# 1_P1_schdoc.net
KiCad netlist of a schematic drawn in Altium Designer
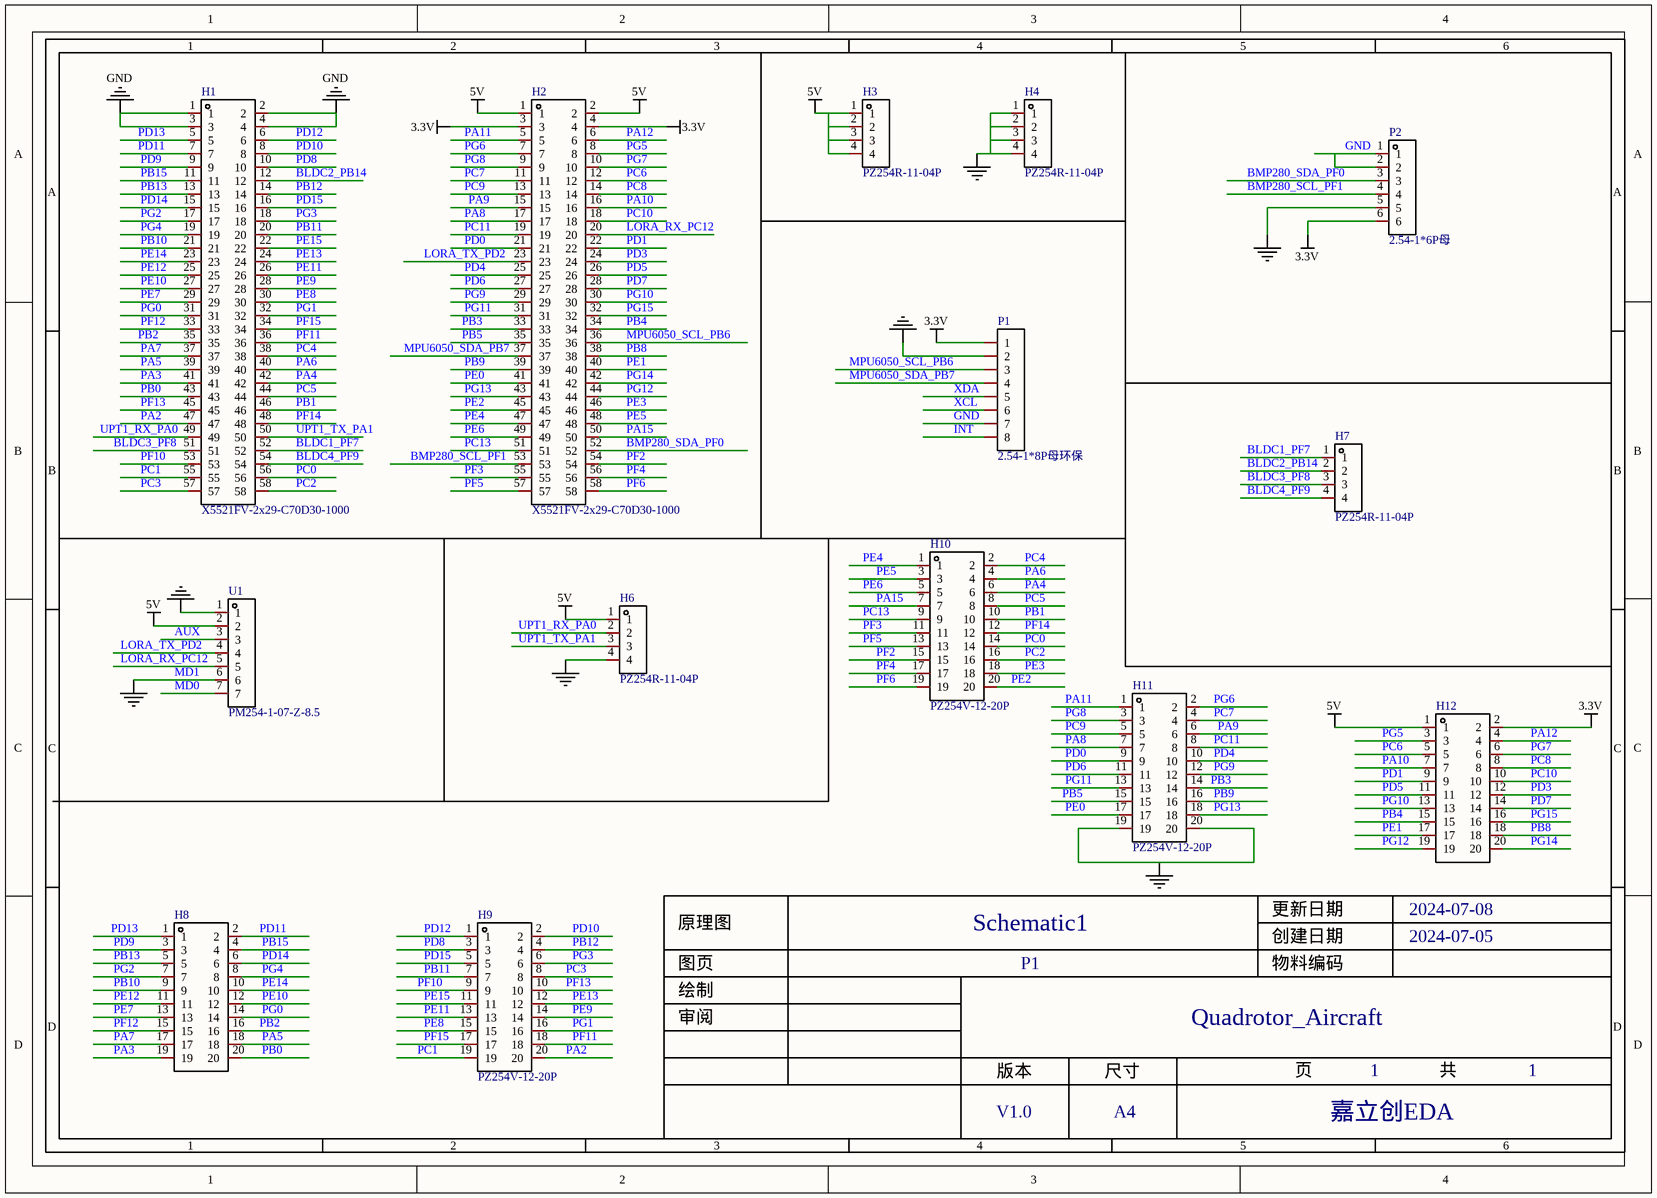
[diagram p0: 1_P1.schdoc.schdoc]

(export (version "E")
  (design (tool "Eeschema 10.0.6"))
  (components
    (comp (ref "H1")
      (value "X5521FV-2x29-C70D30-1000")
      (fields
        (field (name "NAME") "X5521FV-2x29-C70D30-1000")
        (field (name "MANUFACTURER") "XKB Connectivity(中国星坤)")
      )
      (libsource (lib "altium-import") (part "root_0_X5521FV-2x29-C70D30-1000_"))
    )
    (comp (ref "H2")
      (value "X5521FV-2x29-C70D30-1000")
      (fields
        (field (name "NAME") "X5521FV-2x29-C70D30-1000")
        (field (name "MANUFACTURER") "XKB Connectivity(中国星坤)")
      )
      (libsource (lib "altium-import") (part "root_0_X5521FV-2x29-C70D30-1000_"))
    )
    (comp (ref "H3")
      (value "PZ254R-11-04P")
      (fields (field (name "NAME") "PZ254R-11-04P") (field (name "MANUFACTURER") "XFCN(兴飞)"))
      (libsource (lib "altium-import") (part "root_0_PZ254R-11-04P_"))
    )
    (comp (ref "H4")
      (value "PZ254R-11-04P")
      (fields (field (name "NAME") "PZ254R-11-04P") (field (name "MANUFACTURER") "XFCN(兴飞)"))
      (libsource (lib "altium-import") (part "root_0_PZ254R-11-04P_"))
    )
    (comp (ref "H6")
      (value "PZ254R-11-04P")
      (fields (field (name "NAME") "PZ254R-11-04P") (field (name "MANUFACTURER") "XFCN(兴飞)"))
      (libsource (lib "altium-import") (part "root_0_PZ254R-11-04P_"))
    )
    (comp (ref "H7")
      (value "PZ254R-11-04P")
      (fields (field (name "NAME") "PZ254R-11-04P") (field (name "MANUFACTURER") "XFCN(兴飞)"))
      (libsource (lib "altium-import") (part "root_0_PZ254R-11-04P_"))
    )
    (comp (ref "H8")
      (value "PZ254V-12-20P")
      (fields (field (name "MANUFACTURER") "XFCN(兴飞)"))
      (libsource (lib "altium-import") (part "root_0_PZ254V-12-20P_"))
    )
    (comp (ref "H9")
      (value "PZ254V-12-20P")
      (fields (field (name "NAME") "PZ254V-12-20P") (field (name "MANUFACTURER") "XFCN(兴飞)"))
      (libsource (lib "altium-import") (part "root_0_PZ254V-12-20P_"))
    )
    (comp (ref "H10")
      (value "PZ254V-12-20P")
      (fields (field (name "NAME") "PZ254V-12-20P") (field (name "MANUFACTURER") "XFCN(兴飞)"))
      (libsource (lib "altium-import") (part "root_0_PZ254V-12-20P_"))
    )
    (comp (ref "H11")
      (value "PZ254V-12-20P")
      (fields (field (name "NAME") "PZ254V-12-20P") (field (name "MANUFACTURER") "XFCN(兴飞)"))
      (libsource (lib "altium-import") (part "root_0_PZ254V-12-20P_"))
    )
    (comp (ref "H12")
      (value "PZ254V-12-20P")
      (fields (field (name "MANUFACTURER") "XFCN(兴飞)"))
      (libsource (lib "") (part "root_0_PZ254V-12-20P__1"))
    )
    (comp (ref "P1")
      (value "2.54-1*8P母环保")
      (description "插孔结构:1x8P;间距:2.54mm;行距:-;安装类型:直插;排数:单排;总孔位数:8P;塑高:-;触头材质:-;触头镀层:-;")
      (fields (field (name "NAME") "2.54-1*8P母环保") (field (name "MANUFACTURER") "BOOMELE(博穆精密)"))
      (libsource (lib "altium-import") (part "root_0_2.54-1*8P母环保_"))
    )
    (comp (ref "P2")
      (value "2.54-1*6P母")
      (description "插孔结构:1x6P;间距:2.54mm;行距:-;安装类型:直插;排数:单排;总孔位数:6P;塑高:-;触头材质:-;触头镀层:-;")
      (fields (field (name "NAME") "2.54-1*6P母") (field (name "MANUFACTURER") "BOOMELE(博穆精密)"))
      (libsource (lib "altium-import") (part "root_0_2.54-1*6P母_"))
    )
    (comp (ref "U1")
      (value "PM254-1-07-Z-8.5")
      (fields (field (name "NAME") "PM254-1-07-Z-8.5") (field (name "MANUFACTURER") "HCTL(华灿天禄)"))
      (libsource (lib "altium-import") (part "root_0_PM254-1-07-Z-8.5_"))
    )
  )
  (nets
    (net (code "1") (name "/AUX") (class "Default")
      (node (ref "U1") (pin "3") (pinfunction "3_3") (pintype "passive"))
    )
    (net (code "2") (name "/BLDC1_PF7") (class "Default")
      (node (ref "H1") (pin "52") (pinfunction "52_52") (pintype "passive"))
      (node (ref "H7") (pin "1") (pinfunction "1_1") (pintype "passive"))
    )
    (net (code "3") (name "/BLDC2_PB14") (class "Default")
      (node (ref "H1") (pin "12") (pinfunction "12_12") (pintype "passive"))
      (node (ref "H7") (pin "2") (pinfunction "2_2") (pintype "passive"))
    )
    (net (code "4") (name "/BLDC3_PF8") (class "Default")
      (node (ref "H1") (pin "51") (pinfunction "51_51") (pintype "passive"))
      (node (ref "H7") (pin "3") (pinfunction "3_3") (pintype "passive"))
    )
    (net (code "5") (name "/BLDC4_PF9") (class "Default")
      (node (ref "H1") (pin "54") (pinfunction "54_54") (pintype "passive"))
      (node (ref "H7") (pin "4") (pinfunction "4_4") (pintype "passive"))
    )
    (net (code "6") (name "/BMP280_SCL_PF1") (class "Default")
      (node (ref "H2") (pin "53") (pinfunction "53_53") (pintype "passive"))
      (node (ref "P2") (pin "4") (pinfunction "4_4") (pintype "passive"))
    )
    (net (code "7") (name "/BMP280_SDA_PF0") (class "Default")
      (node (ref "H2") (pin "52") (pinfunction "52_52") (pintype "passive"))
      (node (ref "P2") (pin "3") (pinfunction "3_3") (pintype "passive"))
    )
    (net (code "8") (name "/INT") (class "Default")
      (node (ref "P1") (pin "8") (pinfunction "8_8") (pintype "passive"))
    )
    (net (code "9") (name "/LORA_RX_PC12") (class "Default")
      (node (ref "H2") (pin "20") (pinfunction "20_20") (pintype "passive"))
      (node (ref "U1") (pin "5") (pinfunction "5_5") (pintype "passive"))
    )
    (net (code "10") (name "/LORA_TX_PD2") (class "Default")
      (node (ref "H2") (pin "23") (pinfunction "23_23") (pintype "passive"))
      (node (ref "U1") (pin "4") (pinfunction "4_4") (pintype "passive"))
    )
    (net (code "11") (name "/MD0") (class "Default")
      (node (ref "U1") (pin "7") (pinfunction "7_7") (pintype "passive"))
    )
    (net (code "12") (name "/MPU6050_SCL_PB6") (class "Default")
      (node (ref "H2") (pin "36") (pinfunction "36_36") (pintype "passive"))
      (node (ref "P1") (pin "3") (pinfunction "3_3") (pintype "passive"))
    )
    (net (code "13") (name "/MPU6050_SDA_PB7") (class "Default")
      (node (ref "H2") (pin "37") (pinfunction "37_37") (pintype "passive"))
      (node (ref "P1") (pin "4") (pinfunction "4_4") (pintype "passive"))
    )
    (net (code "14") (name "/PA2") (class "Default")
      (node (ref "H1") (pin "47") (pinfunction "47_47") (pintype "passive"))
      (node (ref "H9") (pin "20") (pinfunction "20_20") (pintype "passive"))
    )
    (net (code "15") (name "/PA3") (class "Default")
      (node (ref "H1") (pin "41") (pinfunction "41_41") (pintype "passive"))
      (node (ref "H8") (pin "19") (pinfunction "19_19") (pintype "passive"))
    )
    (net (code "16") (name "/PA4") (class "Default")
      (node (ref "H1") (pin "42") (pinfunction "42_42") (pintype "passive"))
      (node (ref "H10") (pin "6") (pinfunction "6_6") (pintype "passive"))
    )
    (net (code "17") (name "/PA5") (class "Default")
      (node (ref "H1") (pin "39") (pinfunction "39_39") (pintype "passive"))
      (node (ref "H8") (pin "18") (pinfunction "18_18") (pintype "passive"))
    )
    (net (code "18") (name "/PA6") (class "Default")
      (node (ref "H1") (pin "40") (pinfunction "40_40") (pintype "passive"))
      (node (ref "H10") (pin "4") (pinfunction "4_4") (pintype "passive"))
    )
    (net (code "19") (name "/PA7") (class "Default")
      (node (ref "H1") (pin "37") (pinfunction "37_37") (pintype "passive"))
      (node (ref "H8") (pin "17") (pinfunction "17_17") (pintype "passive"))
    )
    (net (code "20") (name "/PA8") (class "Default")
      (node (ref "H11") (pin "7") (pinfunction "7_7") (pintype "passive"))
      (node (ref "H2") (pin "17") (pinfunction "17_17") (pintype "passive"))
    )
    (net (code "21") (name "/PA9") (class "Default")
      (node (ref "H11") (pin "6") (pinfunction "6_6") (pintype "passive"))
      (node (ref "H2") (pin "15") (pinfunction "15_15") (pintype "passive"))
    )
    (net (code "22") (name "/PA10") (class "Default")
      (node (ref "H12") (pin "7") (pinfunction "7_7") (pintype "passive"))
      (node (ref "H2") (pin "16") (pinfunction "16_16") (pintype "passive"))
    )
    (net (code "23") (name "/PA11") (class "Default")
      (node (ref "H11") (pin "1") (pinfunction "1_1") (pintype "passive"))
      (node (ref "H2") (pin "5") (pinfunction "5_5") (pintype "passive"))
    )
    (net (code "24") (name "/PA12") (class "Default")
      (node (ref "H12") (pin "4") (pinfunction "4_4") (pintype "passive"))
      (node (ref "H2") (pin "6") (pinfunction "6_6") (pintype "passive"))
    )
    (net (code "25") (name "/PA15") (class "Default")
      (node (ref "H10") (pin "7") (pinfunction "7_7") (pintype "passive"))
      (node (ref "H2") (pin "50") (pinfunction "50_50") (pintype "passive"))
    )
    (net (code "26") (name "/PB0") (class "Default")
      (node (ref "H1") (pin "43") (pinfunction "43_43") (pintype "passive"))
      (node (ref "H8") (pin "20") (pinfunction "20_20") (pintype "passive"))
    )
    (net (code "27") (name "/PB1") (class "Default")
      (node (ref "H1") (pin "46") (pinfunction "46_46") (pintype "passive"))
      (node (ref "H10") (pin "10") (pinfunction "10_10") (pintype "passive"))
    )
    (net (code "28") (name "/PB2") (class "Default")
      (node (ref "H1") (pin "35") (pinfunction "35_35") (pintype "passive"))
      (node (ref "H8") (pin "16") (pinfunction "16_16") (pintype "passive"))
    )
    (net (code "29") (name "/PB3") (class "Default")
      (node (ref "H11") (pin "14") (pinfunction "14_14") (pintype "passive"))
      (node (ref "H2") (pin "33") (pinfunction "33_33") (pintype "passive"))
    )
    (net (code "30") (name "/PB4") (class "Default")
      (node (ref "H12") (pin "15") (pinfunction "15_15") (pintype "passive"))
      (node (ref "H2") (pin "34") (pinfunction "34_34") (pintype "passive"))
    )
    (net (code "31") (name "/PB5") (class "Default")
      (node (ref "H11") (pin "15") (pinfunction "15_15") (pintype "passive"))
      (node (ref "H2") (pin "35") (pinfunction "35_35") (pintype "passive"))
    )
    (net (code "32") (name "/PB8") (class "Default")
      (node (ref "H12") (pin "18") (pinfunction "18_18") (pintype "passive"))
      (node (ref "H2") (pin "38") (pinfunction "38_38") (pintype "passive"))
    )
    (net (code "33") (name "/PB9") (class "Default")
      (node (ref "H11") (pin "16") (pinfunction "16_16") (pintype "passive"))
      (node (ref "H2") (pin "39") (pinfunction "39_39") (pintype "passive"))
    )
    (net (code "34") (name "/PB10") (class "Default")
      (node (ref "H1") (pin "21") (pinfunction "21_21") (pintype "passive"))
      (node (ref "H8") (pin "9") (pinfunction "9_9") (pintype "passive"))
    )
    (net (code "35") (name "/PB11") (class "Default")
      (node (ref "H1") (pin "20") (pinfunction "20_20") (pintype "passive"))
      (node (ref "H9") (pin "7") (pinfunction "7_7") (pintype "passive"))
    )
    (net (code "36") (name "/PB12") (class "Default")
      (node (ref "H1") (pin "14") (pinfunction "14_14") (pintype "passive"))
      (node (ref "H9") (pin "4") (pinfunction "4_4") (pintype "passive"))
    )
    (net (code "37") (name "/PB13") (class "Default")
      (node (ref "H1") (pin "13") (pinfunction "13_13") (pintype "passive"))
      (node (ref "H8") (pin "5") (pinfunction "5_5") (pintype "passive"))
    )
    (net (code "38") (name "/PB15") (class "Default")
      (node (ref "H1") (pin "11") (pinfunction "11_11") (pintype "passive"))
      (node (ref "H8") (pin "4") (pinfunction "4_4") (pintype "passive"))
    )
    (net (code "39") (name "/PC0") (class "Default")
      (node (ref "H1") (pin "56") (pinfunction "56_56") (pintype "passive"))
      (node (ref "H10") (pin "14") (pinfunction "14_14") (pintype "passive"))
    )
    (net (code "40") (name "/PC1") (class "Default")
      (node (ref "H1") (pin "55") (pinfunction "55_55") (pintype "passive"))
      (node (ref "H9") (pin "19") (pinfunction "19_19") (pintype "passive"))
    )
    (net (code "41") (name "/PC2") (class "Default")
      (node (ref "H1") (pin "58") (pinfunction "58_58") (pintype "passive"))
      (node (ref "H10") (pin "16") (pinfunction "16_16") (pintype "passive"))
    )
    (net (code "42") (name "/PC3") (class "Default")
      (node (ref "H1") (pin "57") (pinfunction "57_57") (pintype "passive"))
      (node (ref "H9") (pin "8") (pinfunction "8_8") (pintype "passive"))
    )
    (net (code "43") (name "/PC4") (class "Default")
      (node (ref "H1") (pin "38") (pinfunction "38_38") (pintype "passive"))
      (node (ref "H10") (pin "2") (pinfunction "2_2") (pintype "passive"))
    )
    (net (code "44") (name "/PC5") (class "Default")
      (node (ref "H1") (pin "44") (pinfunction "44_44") (pintype "passive"))
      (node (ref "H10") (pin "8") (pinfunction "8_8") (pintype "passive"))
    )
    (net (code "45") (name "/PC6") (class "Default")
      (node (ref "H12") (pin "5") (pinfunction "5_5") (pintype "passive"))
      (node (ref "H2") (pin "12") (pinfunction "12_12") (pintype "passive"))
    )
    (net (code "46") (name "/PC7") (class "Default")
      (node (ref "H11") (pin "4") (pinfunction "4_4") (pintype "passive"))
      (node (ref "H2") (pin "11") (pinfunction "11_11") (pintype "passive"))
    )
    (net (code "47") (name "/PC8") (class "Default")
      (node (ref "H12") (pin "8") (pinfunction "8_8") (pintype "passive"))
      (node (ref "H2") (pin "14") (pinfunction "14_14") (pintype "passive"))
    )
    (net (code "48") (name "/PC9") (class "Default")
      (node (ref "H11") (pin "5") (pinfunction "5_5") (pintype "passive"))
      (node (ref "H2") (pin "13") (pinfunction "13_13") (pintype "passive"))
    )
    (net (code "49") (name "/PC10") (class "Default")
      (node (ref "H12") (pin "10") (pinfunction "10_10") (pintype "passive"))
      (node (ref "H2") (pin "18") (pinfunction "18_18") (pintype "passive"))
    )
    (net (code "50") (name "/PC11") (class "Default")
      (node (ref "H11") (pin "8") (pinfunction "8_8") (pintype "passive"))
      (node (ref "H2") (pin "19") (pinfunction "19_19") (pintype "passive"))
    )
    (net (code "51") (name "/PC13") (class "Default")
      (node (ref "H10") (pin "9") (pinfunction "9_9") (pintype "passive"))
      (node (ref "H2") (pin "51") (pinfunction "51_51") (pintype "passive"))
    )
    (net (code "52") (name "/PD0") (class "Default")
      (node (ref "H11") (pin "9") (pinfunction "9_9") (pintype "passive"))
      (node (ref "H2") (pin "21") (pinfunction "21_21") (pintype "passive"))
    )
    (net (code "53") (name "/PD1") (class "Default")
      (node (ref "H12") (pin "9") (pinfunction "9_9") (pintype "passive"))
      (node (ref "H2") (pin "22") (pinfunction "22_22") (pintype "passive"))
    )
    (net (code "54") (name "/PD3") (class "Default")
      (node (ref "H12") (pin "12") (pinfunction "12_12") (pintype "passive"))
      (node (ref "H2") (pin "24") (pinfunction "24_24") (pintype "passive"))
    )
    (net (code "55") (name "/PD4") (class "Default")
      (node (ref "H11") (pin "10") (pinfunction "10_10") (pintype "passive"))
      (node (ref "H2") (pin "25") (pinfunction "25_25") (pintype "passive"))
    )
    (net (code "56") (name "/PD5") (class "Default")
      (node (ref "H12") (pin "11") (pinfunction "11_11") (pintype "passive"))
      (node (ref "H2") (pin "26") (pinfunction "26_26") (pintype "passive"))
    )
    (net (code "57") (name "/PD6") (class "Default")
      (node (ref "H11") (pin "11") (pinfunction "11_11") (pintype "passive"))
      (node (ref "H2") (pin "27") (pinfunction "27_27") (pintype "passive"))
    )
    (net (code "58") (name "/PD7") (class "Default")
      (node (ref "H12") (pin "14") (pinfunction "14_14") (pintype "passive"))
      (node (ref "H2") (pin "28") (pinfunction "28_28") (pintype "passive"))
    )
    (net (code "59") (name "/PD8") (class "Default")
      (node (ref "H1") (pin "10") (pinfunction "10_10") (pintype "passive"))
      (node (ref "H9") (pin "3") (pinfunction "3_3") (pintype "passive"))
    )
    (net (code "60") (name "/PD9") (class "Default")
      (node (ref "H1") (pin "9") (pinfunction "9_9") (pintype "passive"))
      (node (ref "H8") (pin "3") (pinfunction "3_3") (pintype "passive"))
    )
    (net (code "61") (name "/PD10") (class "Default")
      (node (ref "H1") (pin "8") (pinfunction "8_8") (pintype "passive"))
      (node (ref "H9") (pin "2") (pinfunction "2_2") (pintype "passive"))
    )
    (net (code "62") (name "/PD11") (class "Default")
      (node (ref "H1") (pin "7") (pinfunction "7_7") (pintype "passive"))
      (node (ref "H8") (pin "2") (pinfunction "2_2") (pintype "passive"))
    )
    (net (code "63") (name "/PD12") (class "Default")
      (node (ref "H1") (pin "6") (pinfunction "6_6") (pintype "passive"))
      (node (ref "H9") (pin "1") (pinfunction "1_1") (pintype "passive"))
    )
    (net (code "64") (name "/PD13") (class "Default")
      (node (ref "H1") (pin "5") (pinfunction "5_5") (pintype "passive"))
      (node (ref "H8") (pin "1") (pinfunction "1_1") (pintype "passive"))
    )
    (net (code "65") (name "/PD14") (class "Default")
      (node (ref "H1") (pin "15") (pinfunction "15_15") (pintype "passive"))
      (node (ref "H8") (pin "6") (pinfunction "6_6") (pintype "passive"))
    )
    (net (code "66") (name "/PD15") (class "Default")
      (node (ref "H1") (pin "16") (pinfunction "16_16") (pintype "passive"))
      (node (ref "H9") (pin "5") (pinfunction "5_5") (pintype "passive"))
    )
    (net (code "67") (name "/PE0") (class "Default")
      (node (ref "H11") (pin "17") (pinfunction "17_17") (pintype "passive"))
      (node (ref "H2") (pin "41") (pinfunction "41_41") (pintype "passive"))
    )
    (net (code "68") (name "/PE1") (class "Default")
      (node (ref "H12") (pin "17") (pinfunction "17_17") (pintype "passive"))
      (node (ref "H2") (pin "40") (pinfunction "40_40") (pintype "passive"))
    )
    (net (code "69") (name "/PE2") (class "Default")
      (node (ref "H10") (pin "20") (pinfunction "20_20") (pintype "passive"))
      (node (ref "H2") (pin "45") (pinfunction "45_45") (pintype "passive"))
    )
    (net (code "70") (name "/PE3") (class "Default")
      (node (ref "H10") (pin "18") (pinfunction "18_18") (pintype "passive"))
      (node (ref "H2") (pin "46") (pinfunction "46_46") (pintype "passive"))
    )
    (net (code "71") (name "/PE4") (class "Default")
      (node (ref "H10") (pin "1") (pinfunction "1_1") (pintype "passive"))
      (node (ref "H2") (pin "47") (pinfunction "47_47") (pintype "passive"))
    )
    (net (code "72") (name "/PE5") (class "Default")
      (node (ref "H10") (pin "3") (pinfunction "3_3") (pintype "passive"))
      (node (ref "H2") (pin "48") (pinfunction "48_48") (pintype "passive"))
    )
    (net (code "73") (name "/PE6") (class "Default")
      (node (ref "H10") (pin "5") (pinfunction "5_5") (pintype "passive"))
      (node (ref "H2") (pin "49") (pinfunction "49_49") (pintype "passive"))
    )
    (net (code "74") (name "/PE7") (class "Default")
      (node (ref "H1") (pin "29") (pinfunction "29_29") (pintype "passive"))
      (node (ref "H8") (pin "13") (pinfunction "13_13") (pintype "passive"))
    )
    (net (code "75") (name "/PE8") (class "Default")
      (node (ref "H1") (pin "30") (pinfunction "30_30") (pintype "passive"))
      (node (ref "H9") (pin "15") (pinfunction "15_15") (pintype "passive"))
    )
    (net (code "76") (name "/PE9") (class "Default")
      (node (ref "H1") (pin "28") (pinfunction "28_28") (pintype "passive"))
      (node (ref "H9") (pin "14") (pinfunction "14_14") (pintype "passive"))
    )
    (net (code "77") (name "/PE10") (class "Default")
      (node (ref "H1") (pin "27") (pinfunction "27_27") (pintype "passive"))
      (node (ref "H8") (pin "12") (pinfunction "12_12") (pintype "passive"))
    )
    (net (code "78") (name "/PE11") (class "Default")
      (node (ref "H1") (pin "26") (pinfunction "26_26") (pintype "passive"))
      (node (ref "H9") (pin "13") (pinfunction "13_13") (pintype "passive"))
    )
    (net (code "79") (name "/PE12") (class "Default")
      (node (ref "H1") (pin "25") (pinfunction "25_25") (pintype "passive"))
      (node (ref "H8") (pin "11") (pinfunction "11_11") (pintype "passive"))
    )
    (net (code "80") (name "/PE13") (class "Default")
      (node (ref "H1") (pin "24") (pinfunction "24_24") (pintype "passive"))
      (node (ref "H9") (pin "12") (pinfunction "12_12") (pintype "passive"))
    )
    (net (code "81") (name "/PE14") (class "Default")
      (node (ref "H1") (pin "23") (pinfunction "23_23") (pintype "passive"))
      (node (ref "H8") (pin "10") (pinfunction "10_10") (pintype "passive"))
    )
    (net (code "82") (name "/PE15") (class "Default")
      (node (ref "H1") (pin "22") (pinfunction "22_22") (pintype "passive"))
      (node (ref "H9") (pin "11") (pinfunction "11_11") (pintype "passive"))
    )
    (net (code "83") (name "/PF2") (class "Default")
      (node (ref "H10") (pin "15") (pinfunction "15_15") (pintype "passive"))
      (node (ref "H2") (pin "54") (pinfunction "54_54") (pintype "passive"))
    )
    (net (code "84") (name "/PF3") (class "Default")
      (node (ref "H10") (pin "11") (pinfunction "11_11") (pintype "passive"))
      (node (ref "H2") (pin "55") (pinfunction "55_55") (pintype "passive"))
    )
    (net (code "85") (name "/PF4") (class "Default")
      (node (ref "H10") (pin "17") (pinfunction "17_17") (pintype "passive"))
      (node (ref "H2") (pin "56") (pinfunction "56_56") (pintype "passive"))
    )
    (net (code "86") (name "/PF5") (class "Default")
      (node (ref "H10") (pin "13") (pinfunction "13_13") (pintype "passive"))
      (node (ref "H2") (pin "57") (pinfunction "57_57") (pintype "passive"))
    )
    (net (code "87") (name "/PF6") (class "Default")
      (node (ref "H10") (pin "19") (pinfunction "19_19") (pintype "passive"))
      (node (ref "H2") (pin "58") (pinfunction "58_58") (pintype "passive"))
    )
    (net (code "88") (name "/PF10") (class "Default")
      (node (ref "H1") (pin "53") (pinfunction "53_53") (pintype "passive"))
      (node (ref "H9") (pin "9") (pinfunction "9_9") (pintype "passive"))
    )
    (net (code "89") (name "/PF11") (class "Default")
      (node (ref "H1") (pin "36") (pinfunction "36_36") (pintype "passive"))
      (node (ref "H9") (pin "18") (pinfunction "18_18") (pintype "passive"))
    )
    (net (code "90") (name "/PF12") (class "Default")
      (node (ref "H1") (pin "33") (pinfunction "33_33") (pintype "passive"))
      (node (ref "H8") (pin "15") (pinfunction "15_15") (pintype "passive"))
    )
    (net (code "91") (name "/PF13") (class "Default")
      (node (ref "H1") (pin "45") (pinfunction "45_45") (pintype "passive"))
      (node (ref "H9") (pin "10") (pinfunction "10_10") (pintype "passive"))
    )
    (net (code "92") (name "/PF14") (class "Default")
      (node (ref "H1") (pin "48") (pinfunction "48_48") (pintype "passive"))
      (node (ref "H10") (pin "12") (pinfunction "12_12") (pintype "passive"))
    )
    (net (code "93") (name "/PF15") (class "Default")
      (node (ref "H1") (pin "34") (pinfunction "34_34") (pintype "passive"))
      (node (ref "H9") (pin "17") (pinfunction "17_17") (pintype "passive"))
    )
    (net (code "94") (name "/PG0") (class "Default")
      (node (ref "H1") (pin "31") (pinfunction "31_31") (pintype "passive"))
      (node (ref "H8") (pin "14") (pinfunction "14_14") (pintype "passive"))
    )
    (net (code "95") (name "/PG1") (class "Default")
      (node (ref "H1") (pin "32") (pinfunction "32_32") (pintype "passive"))
      (node (ref "H9") (pin "16") (pinfunction "16_16") (pintype "passive"))
    )
    (net (code "96") (name "/PG2") (class "Default")
      (node (ref "H1") (pin "17") (pinfunction "17_17") (pintype "passive"))
      (node (ref "H8") (pin "7") (pinfunction "7_7") (pintype "passive"))
    )
    (net (code "97") (name "/PG3") (class "Default")
      (node (ref "H1") (pin "18") (pinfunction "18_18") (pintype "passive"))
      (node (ref "H9") (pin "6") (pinfunction "6_6") (pintype "passive"))
    )
    (net (code "98") (name "/PG4") (class "Default")
      (node (ref "H1") (pin "19") (pinfunction "19_19") (pintype "passive"))
      (node (ref "H8") (pin "8") (pinfunction "8_8") (pintype "passive"))
    )
    (net (code "99") (name "/PG5") (class "Default")
      (node (ref "H12") (pin "3") (pinfunction "3_3") (pintype "passive"))
      (node (ref "H2") (pin "8") (pinfunction "8_8") (pintype "passive"))
    )
    (net (code "100") (name "/PG6") (class "Default")
      (node (ref "H11") (pin "2") (pinfunction "2_2") (pintype "passive"))
      (node (ref "H2") (pin "7") (pinfunction "7_7") (pintype "passive"))
    )
    (net (code "101") (name "/PG7") (class "Default")
      (node (ref "H12") (pin "6") (pinfunction "6_6") (pintype "passive"))
      (node (ref "H2") (pin "10") (pinfunction "10_10") (pintype "passive"))
    )
    (net (code "102") (name "/PG8") (class "Default")
      (node (ref "H11") (pin "3") (pinfunction "3_3") (pintype "passive"))
      (node (ref "H2") (pin "9") (pinfunction "9_9") (pintype "passive"))
    )
    (net (code "103") (name "/PG9") (class "Default")
      (node (ref "H11") (pin "12") (pinfunction "12_12") (pintype "passive"))
      (node (ref "H2") (pin "29") (pinfunction "29_29") (pintype "passive"))
    )
    (net (code "104") (name "/PG10") (class "Default")
      (node (ref "H12") (pin "13") (pinfunction "13_13") (pintype "passive"))
      (node (ref "H2") (pin "30") (pinfunction "30_30") (pintype "passive"))
    )
    (net (code "105") (name "/PG11") (class "Default")
      (node (ref "H11") (pin "13") (pinfunction "13_13") (pintype "passive"))
      (node (ref "H2") (pin "31") (pinfunction "31_31") (pintype "passive"))
    )
    (net (code "106") (name "/PG12") (class "Default")
      (node (ref "H12") (pin "19") (pinfunction "19_19") (pintype "passive"))
      (node (ref "H2") (pin "44") (pinfunction "44_44") (pintype "passive"))
    )
    (net (code "107") (name "/PG13") (class "Default")
      (node (ref "H11") (pin "18") (pinfunction "18_18") (pintype "passive"))
      (node (ref "H2") (pin "43") (pinfunction "43_43") (pintype "passive"))
    )
    (net (code "108") (name "/PG14") (class "Default")
      (node (ref "H12") (pin "20") (pinfunction "20_20") (pintype "passive"))
      (node (ref "H2") (pin "42") (pinfunction "42_42") (pintype "passive"))
    )
    (net (code "109") (name "/PG15") (class "Default")
      (node (ref "H12") (pin "16") (pinfunction "16_16") (pintype "passive"))
      (node (ref "H2") (pin "32") (pinfunction "32_32") (pintype "passive"))
    )
    (net (code "110") (name "/UPT1_RX_PA0") (class "Default")
      (node (ref "H1") (pin "49") (pinfunction "49_49") (pintype "passive"))
      (node (ref "H6") (pin "2") (pinfunction "2_2") (pintype "passive"))
    )
    (net (code "111") (name "/UPT1_TX_PA1") (class "Default")
      (node (ref "H1") (pin "50") (pinfunction "50_50") (pintype "passive"))
      (node (ref "H6") (pin "3") (pinfunction "3_3") (pintype "passive"))
    )
    (net (code "112") (name "/XCL") (class "Default")
      (node (ref "P1") (pin "6") (pinfunction "6_6") (pintype "passive"))
    )
    (net (code "113") (name "/XDA") (class "Default")
      (node (ref "P1") (pin "5") (pinfunction "5_5") (pintype "passive"))
    )
    (net (code "114") (name "3.3V") (class "Default")
      (node (ref "H12") (pin "2") (pinfunction "2_2") (pintype "passive"))
      (node (ref "H2") (pin "3") (pinfunction "3_3") (pintype "passive"))
      (node (ref "H2") (pin "4") (pinfunction "4_4") (pintype "passive"))
      (node (ref "P1") (pin "1") (pinfunction "1_1") (pintype "passive"))
      (node (ref "P2") (pin "6") (pinfunction "6_6") (pintype "passive"))
    )
    (net (code "115") (name "5V") (class "Default")
      (node (ref "H12") (pin "1") (pinfunction "1_1") (pintype "passive"))
      (node (ref "H2") (pin "1") (pinfunction "1_1") (pintype "passive"))
      (node (ref "H2") (pin "2") (pinfunction "2_2") (pintype "passive"))
      (node (ref "H3") (pin "1") (pinfunction "1_1") (pintype "passive"))
      (node (ref "H3") (pin "2") (pinfunction "2_2") (pintype "passive"))
      (node (ref "H3") (pin "3") (pinfunction "3_3") (pintype "passive"))
      (node (ref "H3") (pin "4") (pinfunction "4_4") (pintype "passive"))
      (node (ref "H6") (pin "1") (pinfunction "1_1") (pintype "passive"))
      (node (ref "U1") (pin "2") (pinfunction "2_2") (pintype "passive"))
    )
    (net (code "116") (name "GND") (class "Default")
      (node (ref "H1") (pin "1") (pinfunction "1_1") (pintype "passive"))
      (node (ref "H1") (pin "2") (pinfunction "2_2") (pintype "passive"))
      (node (ref "H1") (pin "3") (pinfunction "3_3") (pintype "passive"))
      (node (ref "H1") (pin "4") (pinfunction "4_4") (pintype "passive"))
      (node (ref "H11") (pin "19") (pinfunction "19_19") (pintype "passive"))
      (node (ref "H11") (pin "20") (pinfunction "20_20") (pintype "passive"))
      (node (ref "H4") (pin "1") (pinfunction "1_1") (pintype "passive"))
      (node (ref "H4") (pin "2") (pinfunction "2_2") (pintype "passive"))
      (node (ref "H4") (pin "3") (pinfunction "3_3") (pintype "passive"))
      (node (ref "H4") (pin "4") (pinfunction "4_4") (pintype "passive"))
      (node (ref "H6") (pin "4") (pinfunction "4_4") (pintype "passive"))
      (node (ref "P1") (pin "2") (pinfunction "2_2") (pintype "passive"))
      (node (ref "P1") (pin "7") (pinfunction "7_7") (pintype "passive"))
      (node (ref "P2") (pin "1") (pinfunction "1_1") (pintype "passive"))
      (node (ref "P2") (pin "2") (pinfunction "2_2") (pintype "passive"))
      (node (ref "P2") (pin "5") (pinfunction "5_5") (pintype "passive"))
      (node (ref "U1") (pin "1") (pinfunction "1_1") (pintype "passive"))
      (node (ref "U1") (pin "6") (pinfunction "6_6") (pintype "passive"))
    )
  )
)
